# Relay.net
KiCad netlist of a schematic drawn in Altium Designer
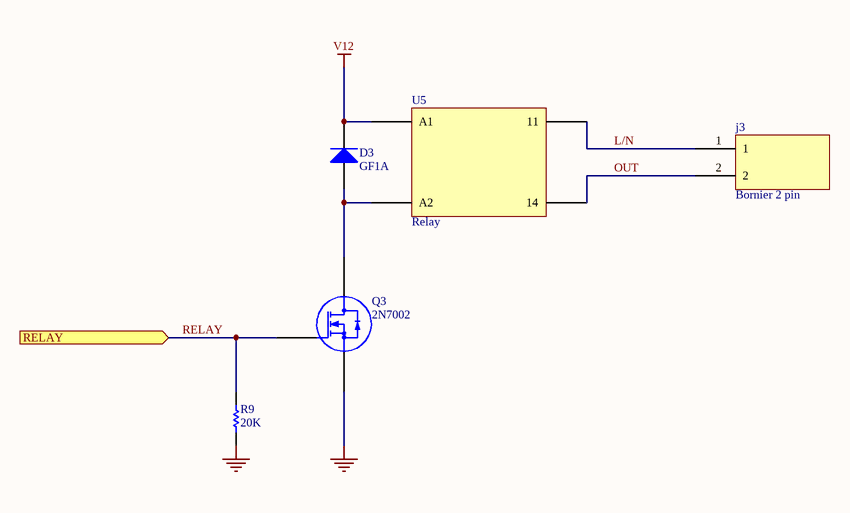
[diagram p0: Relay.SchDoc]

(export (version "E")
  (design (tool "Eeschema 10.0.6"))
  (components
    (comp (ref "D3")
      (value "GF1A")
      (footprint "SMA/DO-214AC_21")
      (description "Default Diode")
      (fields (field (name "PUBLISHER") "Altium Limited"))
      (libsource (lib "Miscellaneous Devices") (part "Diode"))
    )
    (comp (ref "j3")
      (value "Bornier 2 pin")
      (footprint "Bornier 2 pin")
      (libsource (lib "Card_reader") (part "Header 2 pin"))
    )
    (comp (ref "Q3")
      (value "2N7002")
      (footprint "TO-236AB")
      (description "Transistor MOSFET, Canal N, 300 mA, 60 V, 2.8 ohm, 10 V, 2 V")
      (libsource (lib "Card_reader") (part "2N7002"))
    )
    (comp (ref "R9")
      (value "20K")
      (footprint "RES 0603")
      (description "Resistor")
      (fields (field (name "PUBLISHER") "Altium Limited"))
      (libsource (lib "Miscellaneous Devices") (part "Res1"))
    )
    (comp (ref "U5")
      (value "Relay")
      (footprint "Relay")
      (description "Relais de puissance")
      (libsource (lib "Card_reader") (part "Relay"))
    )
  )
  (nets
    (net (code "1") (name "/L{slash}N") (class "Default")
      (node (ref "U5") (pin "11") (pinfunction "11_11") (pintype "passive"))
      (node (ref "j3") (pin "1") (pinfunction "1_1") (pintype "passive"))
    )
    (net (code "2") (name "/OUT") (class "Default")
      (node (ref "U5") (pin "14") (pinfunction "14_14") (pintype "passive"))
      (node (ref "j3") (pin "2") (pinfunction "2_2") (pintype "passive"))
    )
    (net (code "3") (name "/RELAY") (class "Default")
      (node (ref "Q3") (pin "1") (pinfunction "G_1") (pintype "passive"))
      (node (ref "R9") (pin "1") (pinfunction "1_1") (pintype "passive"))
    )
    (net (code "4") (name "GND") (class "Default")
      (node (ref "Q3") (pin "2") (pinfunction "S_2") (pintype "passive"))
      (node (ref "R9") (pin "2") (pinfunction "2_2") (pintype "passive"))
    )
    (net (code "5") (name "Net-(D3-A)") (class "Default")
      (node (ref "D3") (pin "1") (pinfunction "A_1") (pintype "passive"))
      (node (ref "Q3") (pin "3") (pinfunction "D_3") (pintype "passive"))
      (node (ref "U5") (pin "A2") (pinfunction "A2_A2") (pintype "passive"))
    )
    (net (code "6") (name "V12") (class "Default")
      (node (ref "D3") (pin "2") (pinfunction "K_2") (pintype "passive"))
      (node (ref "U5") (pin "A1") (pinfunction "A1_A1") (pintype "passive"))
    )
  )
)
